# thesis.net
KiCad netlist of a schematic drawn in EAGLE
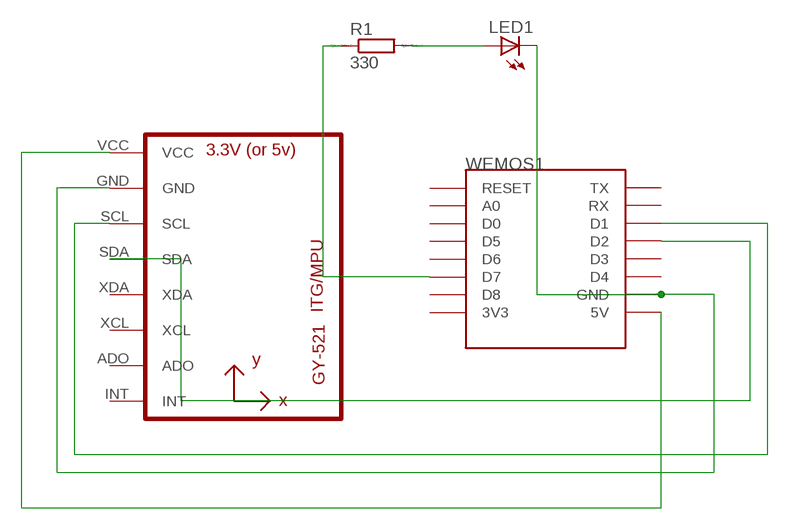
[diagram p0: schematic, sheet 1]

(export (version "E")
  (design (tool "Eeschema 10.0.6"))
  (components
    (comp (ref "LED1")
      (value "LED3MM")
      (footprint "eagle-import:LED3MM")
      (libsource (lib "eagle-import") (part "LED3MM"))
    )
    (comp (ref "R1")
      (value "330")
      (footprint "eagle-import:0204_7")
      (libsource (lib "eagle-import") (part "R0204/7"))
    )
    (comp (ref "U1")
      (value "GY-521MPU6050")
      (footprint "eagle-import:GY-521")
      (libsource (lib "eagle-import") (part "GY-521MPU6050"))
    )
    (comp (ref "WEMOS1")
      (value "WEMOS-D1-MINI")
      (footprint "eagle-import:WEMOS-D1-MINI")
      (libsource (lib "eagle-import") (part "WEMOS-D1-MINI"))
    )
  )
  (nets
    (net (code "1") (name "Net-(LED1-C)") (class "Default")
      (node (ref "LED1") (pin "K") (pinfunction "C_K") (pintype "passive"))
      (node (ref "U1") (pin "GND") (pinfunction "GND_GND") (pintype "bidirectional"))
      (node (ref "WEMOS1") (pin "GND") (pinfunction "GND_GND") (pintype "bidirectional"))
    )
    (net (code "2") (name "Net-(LED1-PadA)") (class "Default")
      (node (ref "LED1") (pin "A") (pinfunction "A_A") (pintype "passive"))
      (node (ref "R1") (pin "2") (pinfunction "2_2") (pintype "passive"))
    )
    (net (code "3") (name "Net-(R1-Pad1)") (class "Default")
      (node (ref "R1") (pin "1") (pinfunction "1_1") (pintype "passive"))
      (node (ref "WEMOS1") (pin "D7") (pinfunction "D7_D7") (pintype "bidirectional"))
    )
    (net (code "4") (name "Net-(U1-PadSCL)") (class "Default")
      (node (ref "U1") (pin "SCL") (pinfunction "SCL_SCL") (pintype "bidirectional"))
      (node (ref "WEMOS1") (pin "D1") (pinfunction "D1_D1") (pintype "bidirectional"))
    )
    (net (code "5") (name "Net-(U1-PadSDA)") (class "Default")
      (node (ref "U1") (pin "SDA") (pinfunction "SDA_SDA") (pintype "bidirectional"))
      (node (ref "WEMOS1") (pin "D2") (pinfunction "D2_D2") (pintype "bidirectional"))
    )
    (net (code "6") (name "Net-(U1-PadVCC)") (class "Default")
      (node (ref "U1") (pin "VCC") (pinfunction "VCC_VCC") (pintype "bidirectional"))
      (node (ref "WEMOS1") (pin "5V") (pinfunction "5V_5V") (pintype "bidirectional"))
    )
    (net (code "7") (name "unconnected-(U1-PadADO)") (class "Default")
      (node (ref "U1") (pin "ADO") (pinfunction "ADO_ADO") (pintype "bidirectional"))
    )
    (net (code "8") (name "unconnected-(U1-PadINT)") (class "Default")
      (node (ref "U1") (pin "INT") (pinfunction "INT_INT") (pintype "bidirectional"))
    )
    (net (code "9") (name "unconnected-(U1-PadXCL)") (class "Default")
      (node (ref "U1") (pin "XCL") (pinfunction "XCL_XCL") (pintype "bidirectional"))
    )
    (net (code "10") (name "unconnected-(U1-PadXDA)") (class "Default")
      (node (ref "U1") (pin "XDA") (pinfunction "XDA_XDA") (pintype "bidirectional"))
    )
    (net (code "11") (name "unconnected-(WEMOS1-Pad3V3)") (class "Default")
      (node (ref "WEMOS1") (pin "3V3") (pinfunction "3V3_3V3") (pintype "bidirectional"))
    )
    (net (code "12") (name "unconnected-(WEMOS1-PadA0)") (class "Default")
      (node (ref "WEMOS1") (pin "A0") (pinfunction "A0_A0") (pintype "bidirectional"))
    )
    (net (code "13") (name "unconnected-(WEMOS1-PadD0)") (class "Default")
      (node (ref "WEMOS1") (pin "D0") (pinfunction "D0_D0") (pintype "bidirectional"))
    )
    (net (code "14") (name "unconnected-(WEMOS1-PadD3)") (class "Default")
      (node (ref "WEMOS1") (pin "D3") (pinfunction "D3_D3") (pintype "bidirectional"))
    )
    (net (code "15") (name "unconnected-(WEMOS1-PadD4)") (class "Default")
      (node (ref "WEMOS1") (pin "D4") (pinfunction "D4_D4") (pintype "bidirectional"))
    )
    (net (code "16") (name "unconnected-(WEMOS1-PadD5)") (class "Default")
      (node (ref "WEMOS1") (pin "D5") (pinfunction "D5_D5") (pintype "bidirectional"))
    )
    (net (code "17") (name "unconnected-(WEMOS1-PadD6)") (class "Default")
      (node (ref "WEMOS1") (pin "D6") (pinfunction "D6_D6") (pintype "bidirectional"))
    )
    (net (code "18") (name "unconnected-(WEMOS1-PadD8)") (class "Default")
      (node (ref "WEMOS1") (pin "D8") (pinfunction "D8_D8") (pintype "bidirectional"))
    )
    (net (code "19") (name "unconnected-(WEMOS1-PadRESET)") (class "Default")
      (node (ref "WEMOS1") (pin "RESET") (pinfunction "RESET_RESET") (pintype "bidirectional"))
    )
    (net (code "20") (name "unconnected-(WEMOS1-PadRX)") (class "Default")
      (node (ref "WEMOS1") (pin "RX") (pinfunction "RX_RX") (pintype "bidirectional"))
    )
    (net (code "21") (name "unconnected-(WEMOS1-PadTX)") (class "Default")
      (node (ref "WEMOS1") (pin "TX") (pinfunction "TX_TX") (pintype "bidirectional"))
    )
  )
)
